# CATS-GS-Sensors.net
KiCad netlist of a schematic drawn in Altium Designer
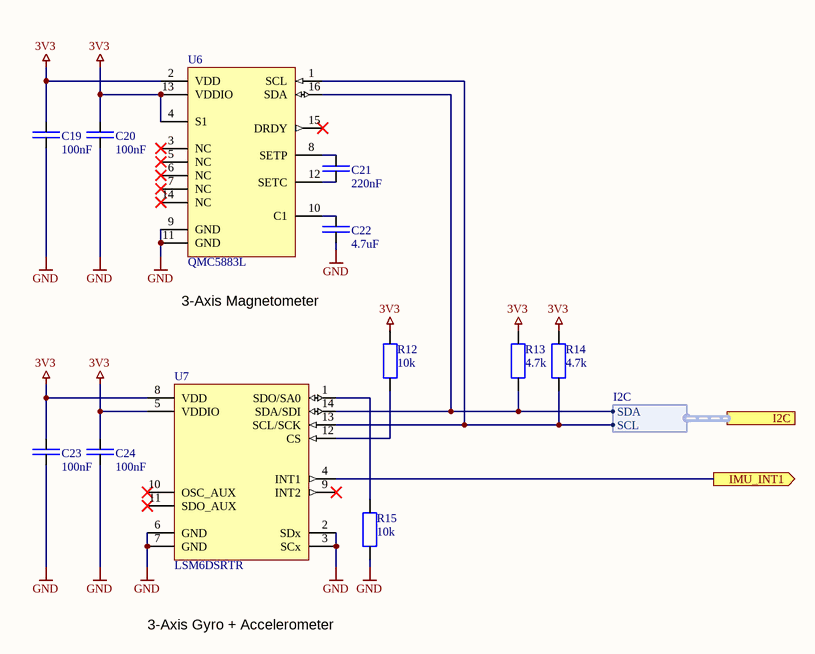
[diagram p0: CATS-GS-Sensors.SchDoc]

(export (version "E")
  (design (tool "Eeschema 10.0.6"))
  (components
    (comp (ref "C19")
      (value "100nF")
      (footprint "SMD Keramikkondensator 0402")
      (description "SMD Ceramic Capacitor E6")
      (libsource (lib "CATS-EUROC") (part "E6 - 100nF"))
    )
    (comp (ref "C20")
      (value "100nF")
      (footprint "SMD Keramikkondensator 0402")
      (description "SMD Ceramic Capacitor E6")
      (libsource (lib "CATS-EUROC") (part "E6 - 100nF"))
    )
    (comp (ref "C21")
      (value "220nF")
      (footprint "SMD Keramikkondensator 0402")
      (description "SMD Ceramic Capacitor E6")
      (libsource (lib "Ceramic Capacitors-E6") (part "E6 - 220nF"))
    )
    (comp (ref "C22")
      (value "4.7uF")
      (footprint "SMD Keramikkondensator 0402")
      (description "SMD Ceramic Capacitor E6")
      (libsource (lib "CATS-EUROC") (part "E6 - 4.7uF"))
    )
    (comp (ref "C23")
      (value "100nF")
      (footprint "SMD Keramikkondensator 0402")
      (description "SMD Ceramic Capacitor E6")
      (libsource (lib "CATS-EUROC") (part "E6 - 100nF"))
    )
    (comp (ref "C24")
      (value "100nF")
      (footprint "SMD Keramikkondensator 0402")
      (description "SMD Ceramic Capacitor E6")
      (libsource (lib "CATS-EUROC") (part "E6 - 100nF"))
    )
    (comp (ref "R12")
      (value "10k")
      (footprint "SMD Widerstand 0402")
      (description "SMD Chip Resistor E24")
      (libsource (lib "Resistors-E24") (part "E24 - 10k"))
    )
    (comp (ref "R13")
      (value "4.7k")
      (footprint "SMD Widerstand 0402")
      (description "SMD Chip Resistor E24")
      (libsource (lib "Resistors-E24") (part "E24 - 4.7k"))
    )
    (comp (ref "R14")
      (value "4.7k")
      (footprint "SMD Widerstand 0402")
      (description "SMD Chip Resistor E24")
      (libsource (lib "Resistors-E24") (part "E24 - 4.7k"))
    )
    (comp (ref "R15")
      (value "10k")
      (footprint "SMD Widerstand 0402")
      (description "SMD Chip Resistor E24")
      (libsource (lib "Resistors-E24") (part "E24 - 10k"))
    )
    (comp (ref "U6")
      (value "QMC5883L")
      (footprint "SMD IC LGA-16 4/4")
      (description "3-Axis Magnetic Sensor")
      (libsource (lib "Sensors") (part "QMC5883L"))
    )
    (comp (ref "U7")
      (value "LSM6DSRTR")
      (footprint "SMD IC LGA-14")
      (description "Accelerometer, Gyroscope, Temperature, 6 Axis Sensor I²C, SPI Output")
      (libsource (lib "Sensors") (part "LSM6DSRTR"))
    )
  )
  (nets
    (net (code "2") (name "/IMU_INT1") (class "Default")
      (node (ref "U7") (pin "4") (pinfunction "INT1_4") (pintype "output"))
    )
    (net (code "4") (name "3V3") (class "Default")
      (node (ref "C19") (pin "2") (pinfunction "2_2") (pintype "passive"))
      (node (ref "C20") (pin "2") (pinfunction "2_2") (pintype "passive"))
      (node (ref "C23") (pin "2") (pinfunction "2_2") (pintype "passive"))
      (node (ref "C24") (pin "2") (pinfunction "2_2") (pintype "passive"))
      (node (ref "R12") (pin "2") (pinfunction "2_2") (pintype "passive"))
      (node (ref "R13") (pin "2") (pinfunction "2_2") (pintype "passive"))
      (node (ref "R14") (pin "2") (pinfunction "2_2") (pintype "passive"))
      (node (ref "U6") (pin "13") (pinfunction "VDDIO_13") (pintype "passive"))
      (node (ref "U6") (pin "2") (pinfunction "VDD_2") (pintype "passive"))
      (node (ref "U6") (pin "4") (pinfunction "S1_4") (pintype "passive"))
      (node (ref "U7") (pin "5") (pinfunction "VDDIO_5") (pintype "passive"))
      (node (ref "U7") (pin "8") (pinfunction "VDD_8") (pintype "passive"))
    )
    (net (code "5") (name "GND") (class "Default")
      (node (ref "C19") (pin "1") (pinfunction "1_1") (pintype "passive"))
      (node (ref "C20") (pin "1") (pinfunction "1_1") (pintype "passive"))
      (node (ref "C22") (pin "1") (pinfunction "1_1") (pintype "passive"))
      (node (ref "C23") (pin "1") (pinfunction "1_1") (pintype "passive"))
      (node (ref "C24") (pin "1") (pinfunction "1_1") (pintype "passive"))
      (node (ref "R15") (pin "1") (pinfunction "1_1") (pintype "passive"))
      (node (ref "U6") (pin "11") (pinfunction "GND_11") (pintype "passive"))
      (node (ref "U6") (pin "9") (pinfunction "GND_9") (pintype "passive"))
      (node (ref "U7") (pin "2") (pinfunction "SDx_2") (pintype "passive"))
      (node (ref "U7") (pin "3") (pinfunction "SCx_3") (pintype "passive"))
      (node (ref "U7") (pin "6") (pinfunction "GND_6") (pintype "passive"))
      (node (ref "U7") (pin "7") (pinfunction "GND_7") (pintype "passive"))
    )
    (net (code "6") (name "Net-(U6-C1)") (class "Default")
      (node (ref "C22") (pin "2") (pinfunction "2_2") (pintype "passive"))
      (node (ref "U6") (pin "10") (pinfunction "C1_10") (pintype "passive"))
    )
    (net (code "7") (name "Net-(U6-SCL)") (class "Default")
      (node (ref "R14") (pin "1") (pinfunction "1_1") (pintype "passive"))
      (node (ref "U6") (pin "1") (pinfunction "SCL_1") (pintype "input"))
      (node (ref "U7") (pin "13") (pinfunction "SCL/SCK_13") (pintype "input"))
    )
    (net (code "8") (name "Net-(U6-SDA)") (class "Default")
      (node (ref "R13") (pin "1") (pinfunction "1_1") (pintype "passive"))
      (node (ref "U6") (pin "16") (pinfunction "SDA_16") (pintype "bidirectional"))
      (node (ref "U7") (pin "14") (pinfunction "SDA/SDI_14") (pintype "bidirectional"))
    )
    (net (code "9") (name "Net-(U6-SETC)") (class "Default")
      (node (ref "C21") (pin "1") (pinfunction "1_1") (pintype "passive"))
      (node (ref "U6") (pin "12") (pinfunction "SETC_12") (pintype "passive"))
    )
    (net (code "10") (name "Net-(U6-SETP)") (class "Default")
      (node (ref "C21") (pin "2") (pinfunction "2_2") (pintype "passive"))
      (node (ref "U6") (pin "8") (pinfunction "SETP_8") (pintype "passive"))
    )
    (net (code "11") (name "Net-(U7-CS)") (class "Default")
      (node (ref "R12") (pin "1") (pinfunction "1_1") (pintype "passive"))
      (node (ref "U7") (pin "12") (pinfunction "CS_12") (pintype "input"))
    )
    (net (code "12") (name "Net-(U7-SDO{slash}SA0)") (class "Default")
      (node (ref "R15") (pin "2") (pinfunction "2_2") (pintype "passive"))
      (node (ref "U7") (pin "1") (pinfunction "SDO/SA0_1") (pintype "bidirectional"))
    )
    (net (code "13") (name "unconnected-(U6-DRDY-Pad15)") (class "Default")
      (node (ref "U6") (pin "15") (pinfunction "DRDY_15") (pintype "output+no_connect"))
    )
    (net (code "14") (name "unconnected-(U6-NC-Pad3)") (class "Default")
      (node (ref "U6") (pin "3") (pinfunction "NC_3") (pintype "passive+no_connect"))
    )
    (net (code "15") (name "unconnected-(U6-NC-Pad5)") (class "Default")
      (node (ref "U6") (pin "5") (pinfunction "NC_5") (pintype "passive+no_connect"))
    )
    (net (code "16") (name "unconnected-(U6-NC-Pad6)") (class "Default")
      (node (ref "U6") (pin "6") (pinfunction "NC_6") (pintype "passive+no_connect"))
    )
    (net (code "17") (name "unconnected-(U6-NC-Pad7)") (class "Default")
      (node (ref "U6") (pin "7") (pinfunction "NC_7") (pintype "passive+no_connect"))
    )
    (net (code "18") (name "unconnected-(U6-NC-Pad14)") (class "Default")
      (node (ref "U6") (pin "14") (pinfunction "NC_14") (pintype "passive+no_connect"))
    )
    (net (code "19") (name "unconnected-(U7-INT2-Pad9)") (class "Default")
      (node (ref "U7") (pin "9") (pinfunction "INT2_9") (pintype "output+no_connect"))
    )
    (net (code "20") (name "unconnected-(U7-OSC_AUX-Pad10)") (class "Default")
      (node (ref "U7") (pin "10") (pinfunction "OSC_AUX_10") (pintype "passive+no_connect"))
    )
    (net (code "21") (name "unconnected-(U7-SDO_AUX-Pad11)") (class "Default")
      (node (ref "U7") (pin "11") (pinfunction "SDO_AUX_11") (pintype "passive+no_connect"))
    )
  )
)
